# led.net
KiCad netlist of a schematic drawn in Altium Designer
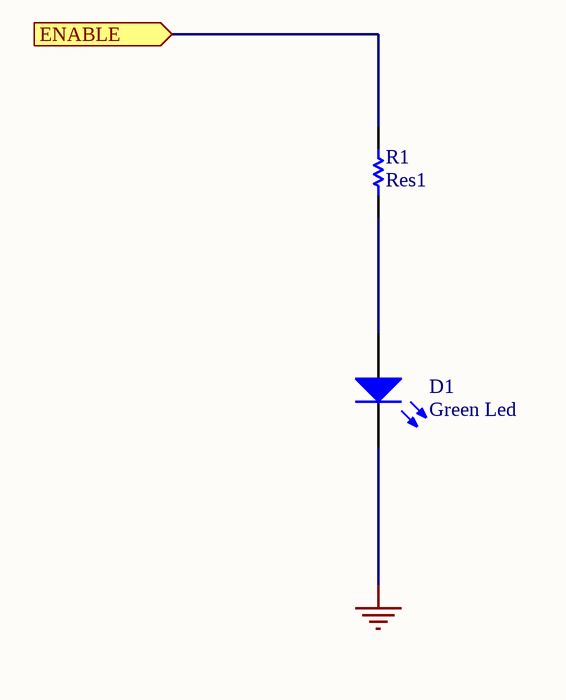
[diagram p0: led.SchDoc]

(export (version "E")
  (design (tool "Eeschema 10.0.6"))
  (components
    (comp (ref "D1")
      (value "Green Led")
      (footprint "LED 0805")
      (description "Typical INFRARED GaAs LED")
      (fields (field (name "PUBLISHER") "Altium Limited"))
      (libsource (lib "Miscellaneous Devices") (part "LED0"))
    )
    (comp (ref "R1")
      (value "Res1")
      (footprint "RESC1608N")
      (description "Resistor")
      (fields (field (name "PUBLISHER") "Altium Limited"))
      (libsource (lib "Miscellaneous Devices") (part "Res1"))
    )
  )
  (nets
    (net (code "1") (name "/ENABLE") (class "Default")
      (node (ref "R1") (pin "2") (pinfunction "2_2") (pintype "passive"))
    )
    (net (code "2") (name "GND") (class "Default")
      (node (ref "D1") (pin "2") (pinfunction "K_2") (pintype "passive"))
    )
    (net (code "3") (name "Net-(D1-A)") (class "Default")
      (node (ref "D1") (pin "1") (pinfunction "A_1") (pintype "passive"))
      (node (ref "R1") (pin "1") (pinfunction "1_1") (pintype "passive"))
    )
  )
)
